# Power.net
KiCad netlist of a schematic drawn in Altium Designer
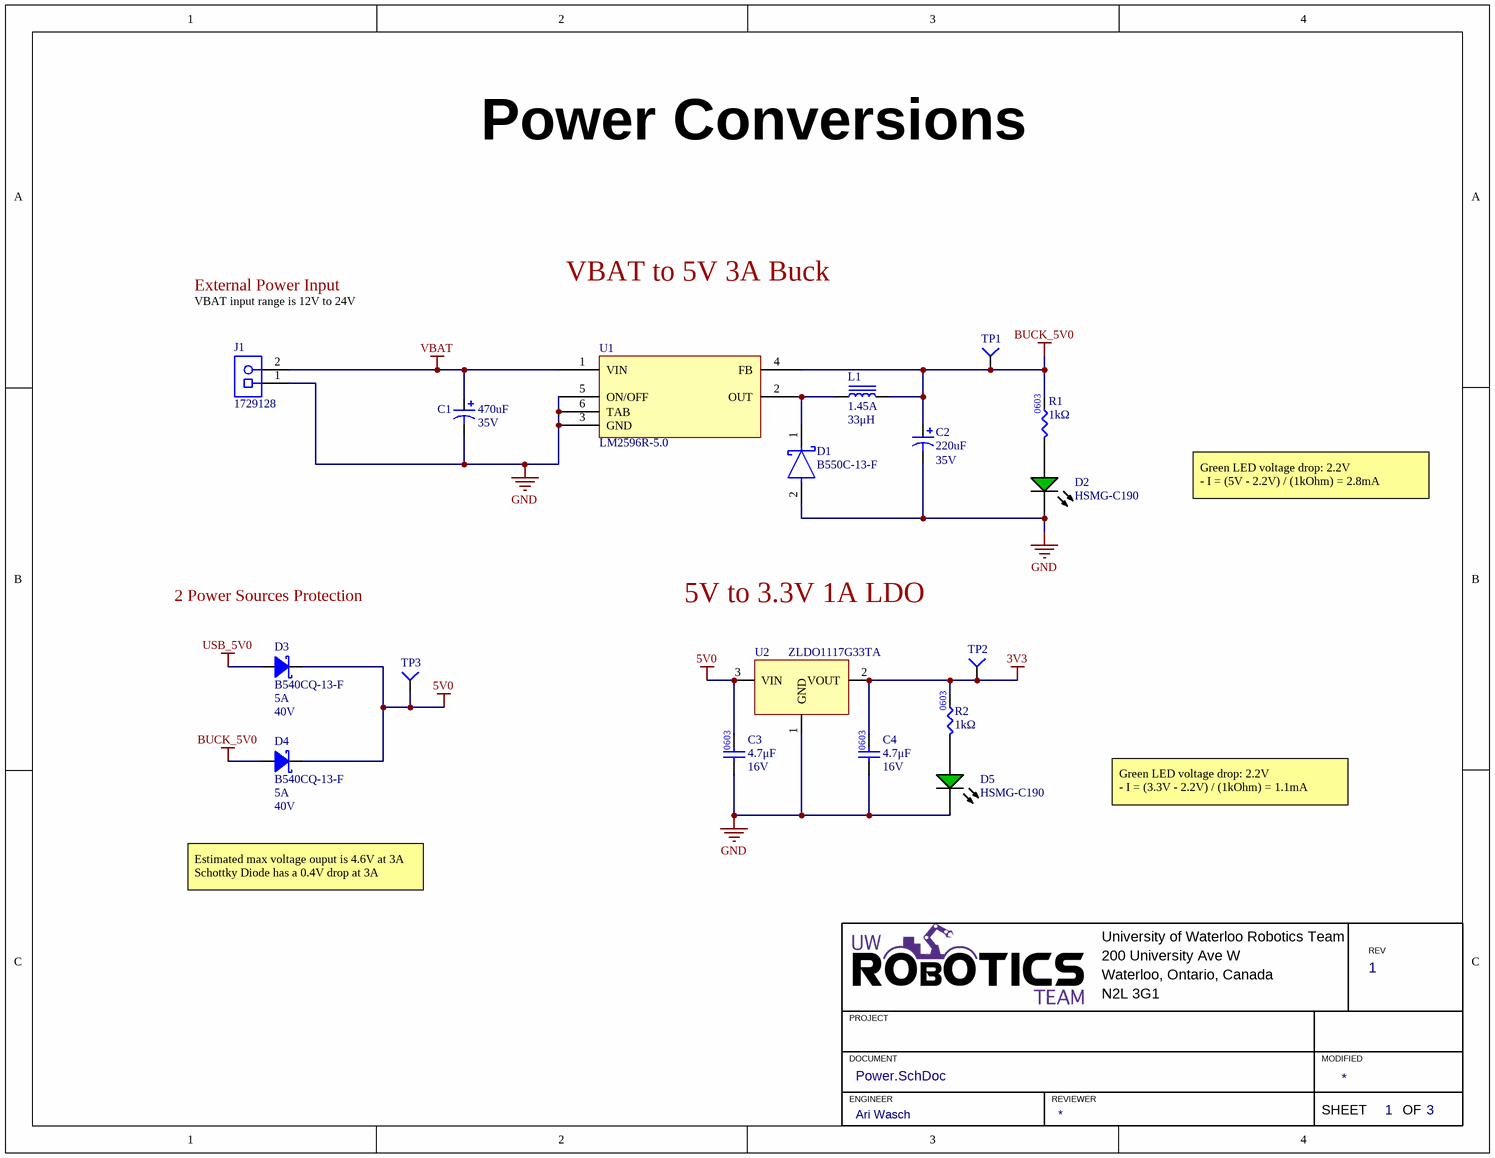
[diagram p0: Power.SchDoc]

(export (version "E")
  (design (tool "Eeschema 10.0.6"))
  (components
    (comp (ref "C1")
      (value "CAP_470uF_35V_ALUM")
      (footprint "CAPAE1030X1100N")
      (description "CAP ALUM 470uF 20% 35V SMD")
      (fields (field (name "VOLTAGE") "35V") (field (name "CAPACITANCE") "470uF"))
      (libsource (lib "UWRT_Schematic_Library_2020") (part "CAP_470uF_35V_ALUM"))
    )
    (comp (ref "C2")
      (value "220uF")
      (footprint "CAP_8x10.2")
      (description "220uF 35V Cap")
      (fields (field (name "MANUFACTURER PART NUMBER") "VT1V221M0810") (field (name "VOLTAGE") "35V"))
      (libsource (lib "UWRT_Schematic_Library_2020") (part "CAP_220uF_35V_ALUM"))
    )
    (comp (ref "C3")
      (value "4.7μF")
      (footprint "CAP0603")
      (description "CAP CER 4.7UF 16V X6S 0603")
      (fields (field (name "VOLTAGE RATING") "16V") (field (name "Comment") "CAP_4.7uF_35V_0603"))
      (libsource (lib "UWRT_Schematic_Library_2020") (part "CAP_4.7uF_35V_0603"))
    )
    (comp (ref "C4")
      (value "4.7μF")
      (footprint "CAP0603")
      (description "CAP CER 4.7UF 16V X6S 0603")
      (fields (field (name "VOLTAGE RATING") "16V") (field (name "Comment") "CAP_4.7uF_35V_0603"))
      (libsource (lib "UWRT_Schematic_Library_2020") (part "CAP_4.7uF_35V_0603"))
    )
    (comp (ref "D1")
      (value "B550C-13-F")
      (footprint "FP-SMC-MFG")
      (description "DIODE SCHOTTKY 50V 5A SMC")
      (libsource (lib "Altium Content Vault") (part "1d6ec82d83fb6aee721767c19dac4b9"))
    )
    (comp (ref "D2")
      (value "HSMG-C190")
      (footprint "AVAG-HSMX-C190_V")
      (description "Chip LED, Green, 2.2 V, -40 to 85 degC, 2-Pin SMD, RoHS, Tape and Reel")
      (libsource (lib "Altium Content Vault") (part "LED-GREEN-AK-2"))
    )
    (comp (ref "D3")
      (value "DIO_SCHOTTKY_40V_5A")
      (footprint "DO214AB SMC")
      (description "DIODE SCHOTTKY 40V 5A SMC")
      (fields
        (field (name "MANUFACTURER PART NUMBER 1") "B540CQ-13-F")
        (field (name "FORWARD CURRENT") "5A")
        (field (name "VOLTAGE") "40V")
      )
      (libsource (lib "UWRT_Schematic_Library_2020") (part "DIO_SCHOTTKY_40V_5A"))
    )
    (comp (ref "D4")
      (value "DIO_SCHOTTKY_40V_5A")
      (footprint "DO214AB SMC")
      (description "DIODE SCHOTTKY 40V 5A SMC")
      (fields
        (field (name "MANUFACTURER PART NUMBER 1") "B540CQ-13-F")
        (field (name "FORWARD CURRENT") "5A")
        (field (name "VOLTAGE") "40V")
      )
      (libsource (lib "UWRT_Schematic_Library_2020") (part "DIO_SCHOTTKY_40V_5A"))
    )
    (comp (ref "D5")
      (value "HSMG-C190")
      (footprint "AVAG-HSMX-C190_V")
      (description "Chip LED, Green, 2.2 V, -40 to 85 degC, 2-Pin SMD, RoHS, Tape and Reel")
      (libsource (lib "Altium Content Vault") (part "LED-GREEN-AK-2"))
    )
    (comp (ref "J1")
      (value "1729128")
      (footprint "PHOE-1729128-2_V")
      (description "PCB Terminal Block, 13.5 A, 400 V, 2-Pin THD, RoHS, Bulk")
      (fields (field (name "MANUFACTURER") "Phoenix Contact"))
      (libsource (lib "Altium Content Vault") (part "CN-2P-F-R2"))
    )
    (comp (ref "L1")
      (value "IND_33uH_1.45A")
      (footprint "IND_CKCS6045")
      (description "INDUCTOR 33UH 1.45A SMD ROHS")
      (fields (field (name "DC CURRENT") "1.45A") (field (name "INDUCTANCE") "33μH"))
      (libsource (lib "UWRT_Schematic_Library_2020") (part "IND_33uH_1.45A"))
    )
    (comp (ref "R1")
      (value "1kΩ")
      (footprint "RES0603")
      (description "RES 1K OHM 5% 1/10W 0603")
      (fields (field (name "Comment") "RES_1kΩ_0603_5%"))
      (libsource (lib "UWRT_Schematic_Library_2020") (part "RES_1kΩ_0603_5%"))
    )
    (comp (ref "R2")
      (value "1kΩ")
      (footprint "RES0603")
      (description "RES 1K OHM 5% 1/10W 0603")
      (fields (field (name "Comment") "RES_1kΩ_0603_5%"))
      (libsource (lib "UWRT_Schematic_Library_2020") (part "RES_1kΩ_0603_5%"))
    )
    (comp (ref "TP1")
      (value "TESTPOINT_1MM_SQUARE")
      (footprint "TESTPOINT_SQUARE_1MM")
      (description "TESTPOINT 1MM SQUARE")
      (libsource (lib "UWRT_Schematic_Library_2020") (part "TESTPOINT_1MM_SQUARE"))
    )
    (comp (ref "TP2")
      (value "TESTPOINT_1MM_SQUARE")
      (footprint "TESTPOINT_SQUARE_1MM")
      (description "TESTPOINT 1MM SQUARE")
      (libsource (lib "UWRT_Schematic_Library_2020") (part "TESTPOINT_1MM_SQUARE"))
    )
    (comp (ref "TP3")
      (value "TESTPOINT_1MM_SQUARE")
      (footprint "TESTPOINT_SQUARE_1MM")
      (description "TESTPOINT 1MM SQUARE")
      (libsource (lib "UWRT_Schematic_Library_2020") (part "TESTPOINT_1MM_SQUARE"))
    )
    (comp (ref "U1")
      (value "LM2596R-5.0")
      (footprint "LM2596S-5.0")
      (description "IC REG BUCK 5V 3A TO220-5")
      (libsource (lib "UWRT_Schematic_Library_2020") (part "LM2596R-5.0"))
    )
    (comp (ref "U2")
      (value "LDO_3.3V_1A")
      (footprint "ZLDO1117G33TA")
      (description "IC REG LINEAR 3.3V 1A SOT223")
      (fields (field (name "SUPPLIER PART NUMBER 1") "ZLDO1117G33TA"))
      (libsource (lib "UWRT_Schematic_Library_2020") (part "LDO_3.3V_1A"))
    )
  )
  (nets
    (net (code "1") (name "3V3") (class "Default")
      (node (ref "C4") (pin "2") (pinfunction "2_2") (pintype "passive"))
      (node (ref "R2") (pin "2") (pinfunction "2_2") (pintype "passive"))
      (node (ref "TP2") (pin "1") (pinfunction "=value_1") (pintype "passive"))
      (node (ref "U2") (pin "2") (pinfunction "VOUT_2") (pintype "passive"))
    )
    (net (code "2") (name "5V0") (class "Default")
      (node (ref "C3") (pin "2") (pinfunction "2_2") (pintype "passive"))
      (node (ref "D3") (pin "2") (pinfunction "Cathode_2") (pintype "passive"))
      (node (ref "D4") (pin "2") (pinfunction "Cathode_2") (pintype "passive"))
      (node (ref "TP3") (pin "1") (pinfunction "=value_1") (pintype "passive"))
      (node (ref "U2") (pin "3") (pinfunction "VIN_3") (pintype "passive"))
    )
    (net (code "3") (name "BUCK_5V0") (class "Default")
      (node (ref "C2") (pin "1") (pinfunction "1_1") (pintype "passive"))
      (node (ref "D4") (pin "1") (pinfunction "Anode_1") (pintype "passive"))
      (node (ref "L1") (pin "2") (pinfunction "2_2") (pintype "passive"))
      (node (ref "R1") (pin "2") (pinfunction "2_2") (pintype "passive"))
      (node (ref "TP1") (pin "1") (pinfunction "=value_1") (pintype "passive"))
      (node (ref "U1") (pin "4") (pinfunction "FB_4") (pintype "passive"))
    )
    (net (code "4") (name "GND") (class "Default")
      (node (ref "C1") (pin "2") (pinfunction "2_2") (pintype "passive"))
      (node (ref "C2") (pin "2") (pinfunction "2_2") (pintype "passive"))
      (node (ref "C3") (pin "1") (pinfunction "1_1") (pintype "passive"))
      (node (ref "C4") (pin "1") (pinfunction "1_1") (pintype "passive"))
      (node (ref "D1") (pin "2") (pinfunction "A_2") (pintype "passive"))
      (node (ref "D2") (pin "2") (pinfunction "K_2") (pintype "passive"))
      (node (ref "D5") (pin "2") (pinfunction "K_2") (pintype "passive"))
      (node (ref "J1") (pin "1") (pinfunction "1_1") (pintype "passive"))
      (node (ref "U1") (pin "3") (pinfunction "GND_3") (pintype "passive"))
      (node (ref "U1") (pin "5") (pinfunction "ON/OFF_5") (pintype "passive"))
      (node (ref "U1") (pin "6") (pinfunction "TAB_6") (pintype "passive"))
      (node (ref "U2") (pin "1") (pinfunction "GND_1") (pintype "passive"))
    )
    (net (code "5") (name "Net-(D1-C)") (class "Default")
      (node (ref "D1") (pin "1") (pinfunction "C_1") (pintype "passive"))
      (node (ref "L1") (pin "1") (pinfunction "1_1") (pintype "passive"))
      (node (ref "U1") (pin "2") (pinfunction "OUT_2") (pintype "passive"))
    )
    (net (code "6") (name "Net-(D2-A)") (class "Default")
      (node (ref "D2") (pin "1") (pinfunction "A_1") (pintype "passive"))
      (node (ref "R1") (pin "1") (pinfunction "1_1") (pintype "passive"))
    )
    (net (code "7") (name "Net-(D5-A)") (class "Default")
      (node (ref "D5") (pin "1") (pinfunction "A_1") (pintype "passive"))
      (node (ref "R2") (pin "1") (pinfunction "1_1") (pintype "passive"))
    )
    (net (code "8") (name "USB_5V0") (class "Default")
      (node (ref "D3") (pin "1") (pinfunction "Anode_1") (pintype "passive"))
    )
    (net (code "9") (name "VBAT") (class "Default")
      (node (ref "C1") (pin "1") (pinfunction "1_1") (pintype "passive"))
      (node (ref "J1") (pin "2") (pinfunction "2_2") (pintype "passive"))
      (node (ref "U1") (pin "1") (pinfunction "VIN_1") (pintype "passive"))
    )
  )
)
